# koosh_sensors.net
KiCad netlist of a schematic drawn in Altium Designer
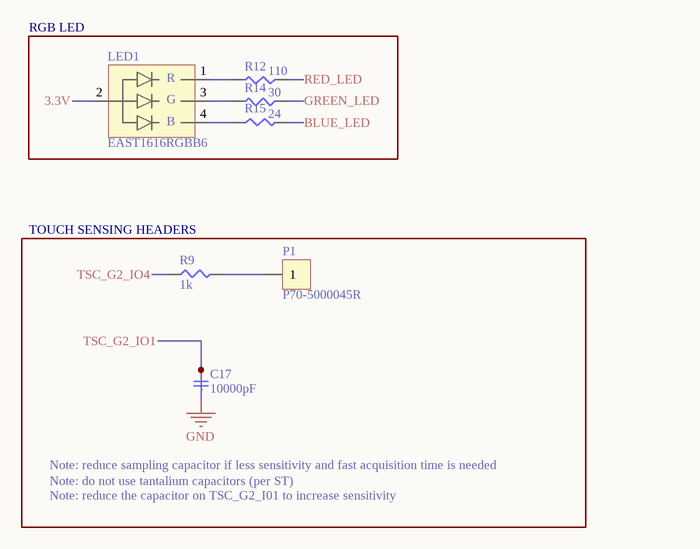
[diagram p0: koosh_sensors.SchDoc]

(export (version "E")
  (design (tool "Eeschema 10.0.6"))
  (components
    (comp (ref "C17")
      (value "10000pF")
      (footprint "SMD-0402C")
      (description "CAP CER 10000PF 50V X7R 0402")
      (fields
        (field (name "DIGI-KEY PART NUMBER") "490-4762-1-ND")
        (field (name "PART NUMBER") "GCM155R71H103KA55D")
      )
      (libsource (lib "capacitor_murata_0402") (part "GCM155R71H103KA55D"))
    )
    (comp (ref "LED1")
      (value "EAST1616RGBB6")
      (footprint "EAST1616RGBB6")
      (libsource (lib "schematic_components") (part "EAST1616RGBB6"))
    )
    (comp (ref "P1")
      (value "P70-5000045R")
      (footprint "P70-5000045R")
      (libsource (lib "schematic_components") (part "P70-5000045R"))
    )
    (comp (ref "R9")
      (value "1k")
      (footprint "SMD-0402-RES")
      (description "RES SMD 1K OHM 5% 1/10W 0402")
      (fields (field (name "PART NUMBER") "ERJ-2GEJ102X") (field (name "DIGI-KEY PART NUMBER") "P1.0KJCT-ND"))
      (libsource (lib "Panasonic_ERJ_0402") (part "ERJ-2GEJ102X"))
    )
    (comp (ref "R12")
      (value "110")
      (footprint "SMD-0402-RES")
      (description "RES SMD 110 OHM 5% 1/10W 0402")
      (fields (field (name "PART NUMBER") "ERJ-2GEJ103X") (field (name "DIGI-KEY PART NUMBER") "P10KJCT-ND"))
      (libsource (lib "Panasonic_ERJ_0402") (part "ERJ-2GEJ103X"))
    )
    (comp (ref "R14")
      (value "30")
      (footprint "SMD-0402-RES")
      (description "RES SMD 110 OHM 5% 1/10W 0402")
      (fields (field (name "PART NUMBER") "ERJ-2GEJ103X") (field (name "DIGI-KEY PART NUMBER") "P10KJCT-ND"))
      (libsource (lib "Panasonic_ERJ_0402") (part "ERJ-2GEJ103X"))
    )
    (comp (ref "R15")
      (value "24")
      (footprint "SMD-0402-RES")
      (description "RES SMD 110 OHM 5% 1/10W 0402")
      (fields (field (name "PART NUMBER") "ERJ-2GEJ103X") (field (name "DIGI-KEY PART NUMBER") "P10KJCT-ND"))
      (libsource (lib "Panasonic_ERJ_0402") (part "ERJ-2GEJ103X"))
    )
  )
  (nets
    (net (code "1") (name "/3.3V") (class "Default")
      (node (ref "LED1") (pin "2") (pinfunction "2_2") (pintype "passive"))
    )
    (net (code "2") (name "/BLUE_LED") (class "Default")
      (node (ref "R15") (pin "2") (pinfunction "2_2") (pintype "passive"))
    )
    (net (code "3") (name "/GREEN_LED") (class "Default")
      (node (ref "R14") (pin "1") (pinfunction "1_1") (pintype "passive"))
    )
    (net (code "4") (name "/RED_LED") (class "Default")
      (node (ref "R12") (pin "1") (pinfunction "1_1") (pintype "passive"))
    )
    (net (code "5") (name "/TSC_G2_IO1") (class "Default")
      (node (ref "C17") (pin "2") (pinfunction "2_2") (pintype "passive"))
    )
    (net (code "6") (name "/TSC_G2_IO4") (class "Default")
      (node (ref "R9") (pin "1") (pinfunction "1_1") (pintype "passive"))
    )
    (net (code "7") (name "GND") (class "Default")
      (node (ref "C17") (pin "1") (pinfunction "1_1") (pintype "passive"))
    )
    (net (code "8") (name "Net-(LED1-Pad1)") (class "Default")
      (node (ref "LED1") (pin "1") (pinfunction "1_1") (pintype "passive"))
      (node (ref "R12") (pin "2") (pinfunction "2_2") (pintype "passive"))
    )
    (net (code "9") (name "Net-(LED1-Pad3)") (class "Default")
      (node (ref "LED1") (pin "3") (pinfunction "3_3") (pintype "passive"))
      (node (ref "R14") (pin "2") (pinfunction "2_2") (pintype "passive"))
    )
    (net (code "10") (name "Net-(LED1-Pad4)") (class "Default")
      (node (ref "LED1") (pin "4") (pinfunction "4_4") (pintype "passive"))
      (node (ref "R15") (pin "1") (pinfunction "1_1") (pintype "passive"))
    )
    (net (code "11") (name "Net-(P1-Pad1)") (class "Default")
      (node (ref "P1") (pin "1") (pinfunction "1_1") (pintype "passive"))
      (node (ref "R9") (pin "2") (pinfunction "2_2") (pintype "passive"))
    )
  )
)
